# Supply_DAC.net
KiCad netlist of a schematic drawn in Altium Designer
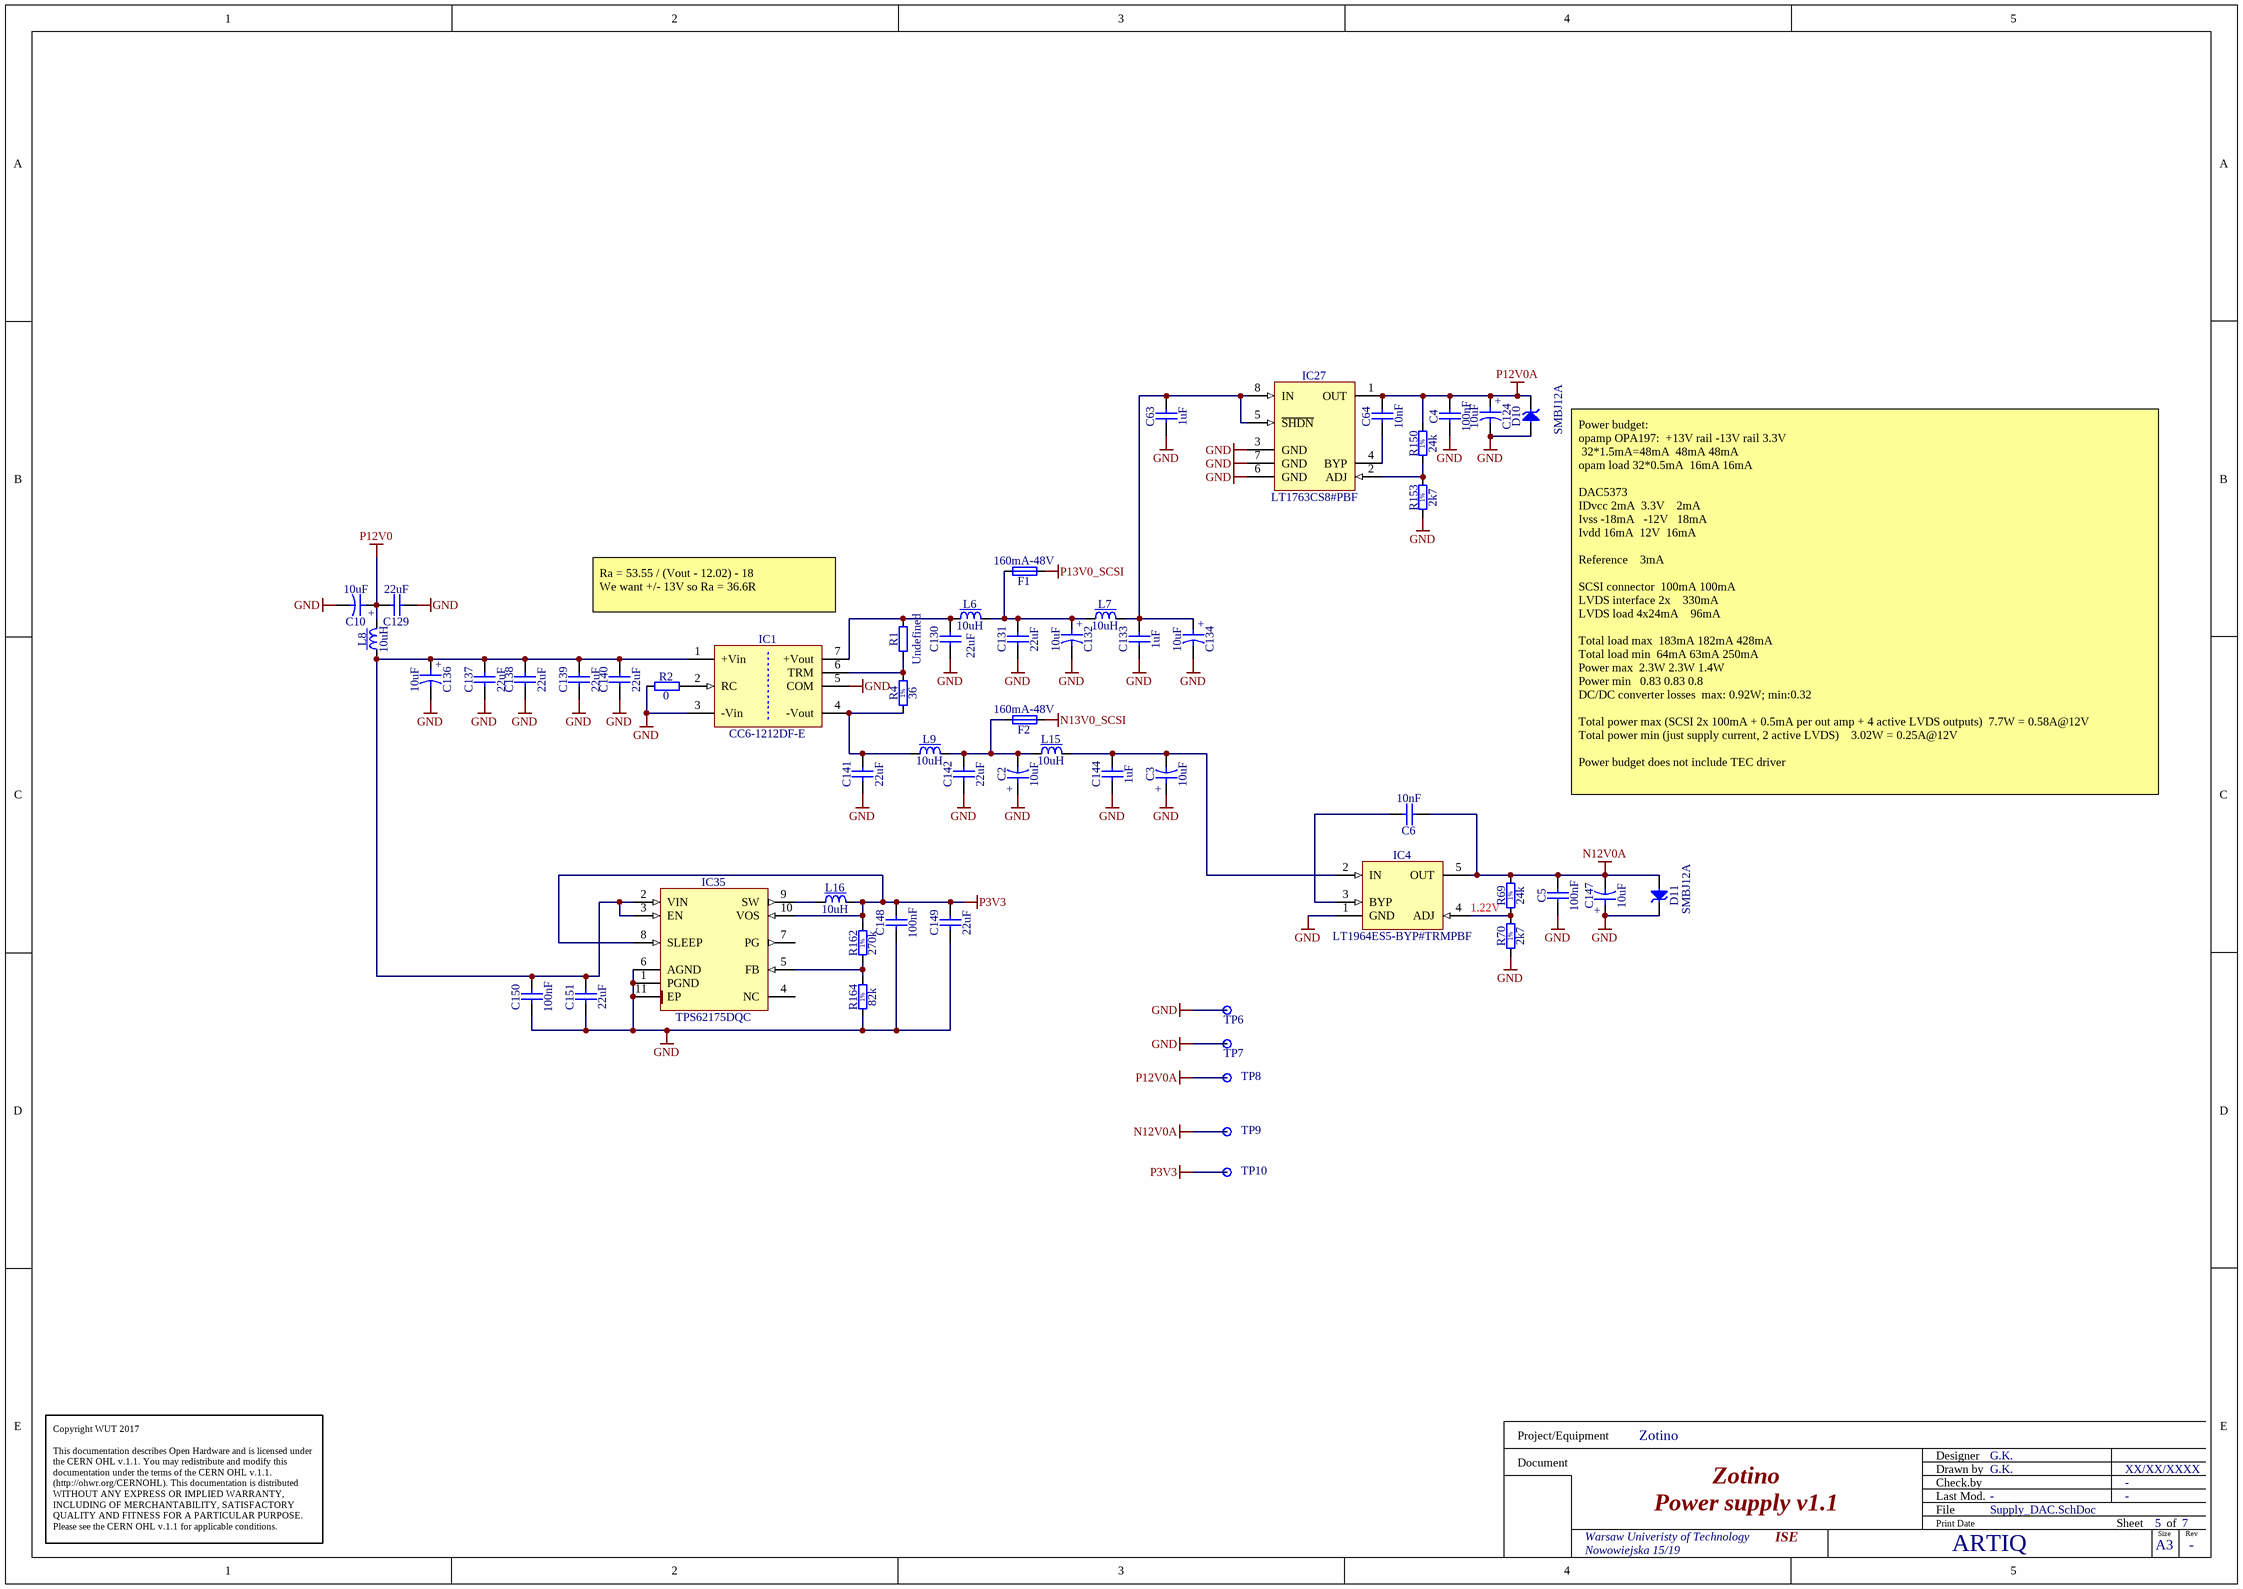
[diagram p0: Supply_DAC.SchDoc]

(export (version "E")
  (design (tool "Eeschema 10.0.6"))
  (components
    (comp (ref "C2")
      (value "10uF")
      (footprint "CAPMP3216X180N")
      (description "Polarised capacitor")
      (fields
        (field (name "PART NUMBER") "CTE3216-18_10UF_16V_20%_AVX_TCJ")
        (field (name "VOLTAGE") "16V")
        (field (name "AUTHOR") "CERN DEM JLC")
      )
      (libsource (lib "Capacitors") (part "Capacitor - polarized"))
    )
    (comp (ref "C3")
      (value "10uF")
      (footprint "CAPMP3216X180N")
      (description "Polarised capacitor")
      (fields
        (field (name "PART NUMBER") "CTE3216-18_10UF_16V_20%_AVX_TCJ")
        (field (name "VOLTAGE") "16V")
        (field (name "AUTHOR") "CERN DEM JLC")
      )
      (libsource (lib "Capacitors") (part "Capacitor - polarized"))
    )
    (comp (ref "C4")
      (value "100nF")
      (footprint "CAPC1005X55N")
      (description "Non-polarised capacitor")
      (fields
        (field (name "PART NUMBER") "CC0402_100NF_16V_10%_X5R")
        (field (name "VOLTAGE") "16V")
        (field (name "AUTHOR") "CERN DEM JLC")
      )
      (libsource (lib "Capacitors") (part "Capacitor - non polarized"))
    )
    (comp (ref "C5")
      (value "100nF")
      (footprint "CAPC1005X55N")
      (description "Non-polarised capacitor")
      (fields
        (field (name "PART NUMBER") "CC0402_100NF_16V_10%_X5R")
        (field (name "VOLTAGE") "16V")
        (field (name "AUTHOR") "CERN DEM JLC")
      )
      (libsource (lib "Capacitors") (part "Capacitor - non polarized"))
    )
    (comp (ref "C6")
      (value "10nF")
      (footprint "CAPC1608X87N")
      (description "Non-polarised capacitor")
      (fields
        (field (name "PART NUMBER") "CC0603_10NF_50V_10%_X7R")
        (field (name "VOLTAGE") "50V")
        (field (name "AUTHOR") "CERN DEM JLC")
      )
      (libsource (lib "Capacitors") (part "Capacitor - non polarized"))
    )
    (comp (ref "C10")
      (value "10uF")
      (footprint "CAPMP3216X180N")
      (description "Polarised capacitor")
      (fields
        (field (name "PART NUMBER") "CTE3216-18_10UF_16V_20%_AVX_TCJ")
        (field (name "VOLTAGE") "16V")
        (field (name "AUTHOR") "CERN DEM JLC")
      )
      (libsource (lib "Capacitors") (part "Capacitor - polarized"))
    )
    (comp (ref "C63")
      (value "1uF")
      (footprint "CAPC1608X87N")
      (description "Non-polarised capacitor")
      (fields
        (field (name "PART NUMBER") "CC0603_1UF_25V_10%_X7R")
        (field (name "VOLTAGE") "25V")
        (field (name "AUTHOR") "CERN DEM JLC")
      )
      (libsource (lib "Capacitors") (part "Capacitor - non polarized"))
    )
    (comp (ref "C64")
      (value "10nF")
      (footprint "CAPC1608X87N")
      (description "Non-polarised capacitor")
      (fields
        (field (name "PART NUMBER") "CC0603_10NF_50V_10%_X7R")
        (field (name "VOLTAGE") "50V")
        (field (name "AUTHOR") "CERN DEM JLC")
      )
      (libsource (lib "Capacitors") (part "Capacitor - non polarized"))
    )
    (comp (ref "C124")
      (value "10uF")
      (footprint "CAPMP3216X180N")
      (description "Polarised capacitor")
      (fields
        (field (name "PART NUMBER") "CTE3216-18_10UF_16V_20%_AVX_TCJ")
        (field (name "VOLTAGE") "16V")
        (field (name "AUTHOR") "CERN DEM JLC")
      )
      (libsource (lib "Capacitors") (part "Capacitor - polarized"))
    )
    (comp (ref "C129")
      (value "22uF")
      (footprint "CAPC2012X135N")
      (description "Non-polarised capacitor")
      (fields
        (field (name "PART NUMBER") "CC0805_22UF_16V_10%_X5R")
        (field (name "VOLTAGE") "16V")
        (field (name "AUTHOR") "CERN DEM JLC")
      )
      (libsource (lib "Capacitors") (part "Capacitor - non polarized"))
    )
    (comp (ref "C130")
      (value "22uF")
      (footprint "CAPC2012X135N")
      (description "Non-polarised capacitor")
      (fields
        (field (name "PART NUMBER") "CC0805_22UF_16V_10%_X5R")
        (field (name "VOLTAGE") "16V")
        (field (name "AUTHOR") "CERN DEM JLC")
      )
      (libsource (lib "Capacitors") (part "Capacitor - non polarized"))
    )
    (comp (ref "C131")
      (value "22uF")
      (footprint "CAPC2012X135N")
      (description "Non-polarised capacitor")
      (fields
        (field (name "PART NUMBER") "CC0805_22UF_16V_10%_X5R")
        (field (name "VOLTAGE") "16V")
        (field (name "AUTHOR") "CERN DEM JLC")
      )
      (libsource (lib "Capacitors") (part "Capacitor - non polarized"))
    )
    (comp (ref "C132")
      (value "10uF")
      (footprint "CAPMP3216X180N")
      (description "Polarised capacitor")
      (fields
        (field (name "PART NUMBER") "CTE3216-18_10UF_16V_20%_AVX_TCJ")
        (field (name "VOLTAGE") "16V")
        (field (name "AUTHOR") "CERN DEM JLC")
      )
      (libsource (lib "Capacitors") (part "Capacitor - polarized"))
    )
    (comp (ref "C133")
      (value "1uF")
      (footprint "CAPC1608X87N")
      (description "Non-polarised capacitor")
      (fields
        (field (name "PART NUMBER") "CC0603_1UF_25V_10%_X7R")
        (field (name "VOLTAGE") "25V")
        (field (name "AUTHOR") "CERN DEM JLC")
      )
      (libsource (lib "Capacitors") (part "Capacitor - non polarized"))
    )
    (comp (ref "C134")
      (value "10uF")
      (footprint "CAPMP3216X180N")
      (description "Polarised capacitor")
      (fields
        (field (name "PART NUMBER") "CTE3216-18_10UF_16V_20%_AVX_TCJ")
        (field (name "VOLTAGE") "16V")
        (field (name "AUTHOR") "CERN DEM JLC")
      )
      (libsource (lib "Capacitors") (part "Capacitor - polarized"))
    )
    (comp (ref "C136")
      (value "10uF")
      (footprint "CAPMP3216X180N")
      (description "Polarised capacitor")
      (fields
        (field (name "PART NUMBER") "CTE3216-18_10UF_16V_20%_AVX_TCJ")
        (field (name "VOLTAGE") "16V")
        (field (name "AUTHOR") "CERN DEM JLC")
      )
      (libsource (lib "Capacitors") (part "Capacitor - polarized"))
    )
    (comp (ref "C137")
      (value "22uF")
      (footprint "CAPC2012X135N")
      (description "Non-polarised capacitor")
      (fields
        (field (name "PART NUMBER") "CC0805_22UF_16V_10%_X5R")
        (field (name "VOLTAGE") "16V")
        (field (name "AUTHOR") "CERN DEM JLC")
      )
      (libsource (lib "Capacitors") (part "Capacitor - non polarized"))
    )
    (comp (ref "C138")
      (value "22uF")
      (footprint "CAPC2012X135N")
      (description "Non-polarised capacitor")
      (fields
        (field (name "PART NUMBER") "CC0805_22UF_16V_10%_X5R")
        (field (name "VOLTAGE") "16V")
        (field (name "AUTHOR") "CERN DEM JLC")
      )
      (libsource (lib "Capacitors") (part "Capacitor - non polarized"))
    )
    (comp (ref "C139")
      (value "22uF")
      (footprint "CAPC2012X135N")
      (description "Non-polarised capacitor")
      (fields
        (field (name "PART NUMBER") "CC0805_22UF_16V_10%_X5R")
        (field (name "VOLTAGE") "16V")
        (field (name "AUTHOR") "CERN DEM JLC")
      )
      (libsource (lib "Capacitors") (part "Capacitor - non polarized"))
    )
    (comp (ref "C140")
      (value "22uF")
      (footprint "CAPC2012X135N")
      (description "Non-polarised capacitor")
      (fields
        (field (name "PART NUMBER") "CC0805_22UF_16V_10%_X5R")
        (field (name "VOLTAGE") "16V")
        (field (name "AUTHOR") "CERN DEM JLC")
      )
      (libsource (lib "Capacitors") (part "Capacitor - non polarized"))
    )
    (comp (ref "C141")
      (value "22uF")
      (footprint "CAPC2012X135N")
      (description "Non-polarised capacitor")
      (fields
        (field (name "PART NUMBER") "CC0805_22UF_16V_10%_X5R")
        (field (name "VOLTAGE") "16V")
        (field (name "AUTHOR") "CERN DEM JLC")
      )
      (libsource (lib "Capacitors") (part "Capacitor - non polarized"))
    )
    (comp (ref "C142")
      (value "22uF")
      (footprint "CAPC2012X135N")
      (description "Non-polarised capacitor")
      (fields
        (field (name "PART NUMBER") "CC0805_22UF_16V_10%_X5R")
        (field (name "VOLTAGE") "16V")
        (field (name "AUTHOR") "CERN DEM JLC")
      )
      (libsource (lib "Capacitors") (part "Capacitor - non polarized"))
    )
    (comp (ref "C144")
      (value "1uF")
      (footprint "CAPC1608X87N")
      (description "Non-polarised capacitor")
      (fields
        (field (name "PART NUMBER") "CC0603_1UF_25V_10%_X7R")
        (field (name "VOLTAGE") "25V")
        (field (name "AUTHOR") "CERN DEM JLC")
      )
      (libsource (lib "Capacitors") (part "Capacitor - non polarized"))
    )
    (comp (ref "C147")
      (value "10uF")
      (footprint "CAPMP3216X180N")
      (description "Polarised capacitor")
      (fields
        (field (name "PART NUMBER") "CTE3216-18_10UF_16V_20%_AVX_TCJ")
        (field (name "VOLTAGE") "16V")
        (field (name "AUTHOR") "CERN DEM JLC")
      )
      (libsource (lib "Capacitors") (part "Capacitor - polarized"))
    )
    (comp (ref "C148")
      (value "100nF")
      (footprint "CAPC1005X55N")
      (description "Non-polarised capacitor")
      (fields
        (field (name "PART NUMBER") "CC0402_100NF_16V_10%_X5R")
        (field (name "VOLTAGE") "16V")
        (field (name "AUTHOR") "CERN DEM JLC")
      )
      (libsource (lib "Capacitors") (part "Capacitor - non polarized"))
    )
    (comp (ref "C149")
      (value "22uF")
      (footprint "CAPC2012X135N")
      (description "Non-polarised capacitor")
      (fields
        (field (name "PART NUMBER") "CC0805_22UF_16V_10%_X5R")
        (field (name "VOLTAGE") "16V")
        (field (name "AUTHOR") "CERN DEM JLC")
      )
      (libsource (lib "Capacitors") (part "Capacitor - non polarized"))
    )
    (comp (ref "C150")
      (value "100nF")
      (footprint "CAPC1005X55N")
      (description "Non-polarised capacitor")
      (fields
        (field (name "PART NUMBER") "CC0402_100NF_16V_10%_X5R")
        (field (name "VOLTAGE") "16V")
        (field (name "AUTHOR") "CERN DEM JLC")
      )
      (libsource (lib "Capacitors") (part "Capacitor - non polarized"))
    )
    (comp (ref "C151")
      (value "22uF")
      (footprint "CAPC2012X135N")
      (description "Non-polarised capacitor")
      (fields
        (field (name "PART NUMBER") "CC0805_22UF_16V_10%_X5R")
        (field (name "VOLTAGE") "16V")
        (field (name "AUTHOR") "CERN DEM JLC")
      )
      (libsource (lib "Capacitors") (part "Capacitor - non polarized"))
    )
    (comp (ref "D10")
      (value "SMBJ12A")
      (footprint "DIOM5336X265N")
      (description "Zener Diode")
      (fields
        (field (name "VOLTAGE") "12V")
        (field (name "POWER") "600W")
        (field (name "AUTHOR") "CERN DEM JLC")
      )
      (libsource (lib "ICs And Semiconductors") (part "Diode Zener"))
    )
    (comp (ref "D11")
      (value "SMBJ12A")
      (footprint "DIOM5336X265N")
      (description "Zener Diode")
      (fields
        (field (name "VOLTAGE") "12V")
        (field (name "POWER") "600W")
        (field (name "AUTHOR") "CERN DEM JLC")
      )
      (libsource (lib "ICs And Semiconductors") (part "Diode Zener"))
    )
    (comp (ref "F1")
      (value "160mA-48V")
      (footprint "FUSRC3216X100N")
      (description "Fuse")
      (fields
        (field (name "PART NUMBER") "FUSR1206_TYCO-NANOSMD016F")
        (field (name "MANUFACTURER") "TYCO ELECTRONICS")
        (field (name "AUTHOR") "CERN DEM JLC")
      )
      (libsource (lib "Eletro-mechanical") (part "Fuse"))
    )
    (comp (ref "F2")
      (value "160mA-48V")
      (footprint "FUSRC3216X100N")
      (description "Fuse")
      (fields
        (field (name "PART NUMBER") "FUSR1206_TYCO-NANOSMD016F")
        (field (name "MANUFACTURER") "TYCO ELECTRONICS")
        (field (name "AUTHOR") "CERN DEM JLC")
      )
      (libsource (lib "Eletro-mechanical") (part "Fuse"))
    )
    (comp (ref "IC1")
      (value "CC6-1212DF-E")
      (footprint "CC6-1212DF-E")
      (description "CONV DC/DC 6W DUAL 12V +-12V PCB")
      (fields (field (name "MANUFACTURER") "TDK-Lambda Americas Inc.") (field (name "AUTHOR") "GK"))
      (libsource (lib "LIBRARY_SCH") (part "DC/DC_CC6-1212DF-E"))
    )
    (comp (ref "IC4")
      (value "LT1964ES5-BYP#TRMPBF")
      (footprint "SOT95P280X100-5N")
      (description "200mA, Low Noise, Low Dropout Negative Micropower Regulator")
      (fields (field (name "MANUFACTURER") "LINEAR TECHNOLOGY") (field (name "AUTHOR") "CERN DEM MR"))
      (libsource (lib "ICs And Semiconductors") (part "LT1964-BYP"))
    )
    (comp (ref "IC27")
      (value "LT1763CS8#PBF")
      (footprint "SOIC127P600X175-8N")
      (description "1.22V to 20V 500mA, Low Noise, LDO Adjustable Micropower Regulator")
      (fields (field (name "MANUFACTURER") "LINEAR TECHNOLOGY") (field (name "AUTHOR") "CERN DEM JLC"))
      (libsource (lib "ICs And Semiconductors") (part "LT1763xS8"))
    )
    (comp (ref "IC35")
      (value "TPS62175DQC")
      (footprint "SON50P200X300X80-11N-R94X250")
      (description "4.75-28VDC to 1-6VDC, 500mA Step-Down Converter With Sleep Mode")
      (fields (field (name "MANUFACTURER") "TEXAS INSTRUMENTS") (field (name "AUTHOR") "CERN DEM JMW"))
      (libsource (lib "ICs And Semiconductors") (part "TPS62175"))
    )
    (comp (ref "L6")
      (value "10uH")
      (footprint "IND_MURATA-PS_8400")
      (description "Inductor With Core")
      (fields
        (field (name "PART NUMBER") "IND_10UH_10%_MURATA-PS_8400")
        (field (name "POWER") "950mA")
        (field (name "AUTHOR") "CERN DEM JLC")
      )
      (libsource (lib "Inductors & Transformers") (part "Inductor With Magnetic core"))
    )
    (comp (ref "L7")
      (value "10uH")
      (footprint "IND_MURATA-PS_8400")
      (description "Inductor With Core")
      (fields
        (field (name "PART NUMBER") "IND_10UH_10%_MURATA-PS_8400")
        (field (name "POWER") "950mA")
        (field (name "AUTHOR") "CERN DEM JLC")
      )
      (libsource (lib "Inductors & Transformers") (part "Inductor With Magnetic core"))
    )
    (comp (ref "L8")
      (value "10uH")
      (footprint "IND_MURATA-PS_8400")
      (description "Inductor With Core")
      (fields
        (field (name "PART NUMBER") "IND_10UH_10%_MURATA-PS_8400")
        (field (name "POWER") "950mA")
        (field (name "AUTHOR") "CERN DEM JLC")
      )
      (libsource (lib "") (part "Inductor With Magnetic core_1"))
    )
    (comp (ref "L9")
      (value "10uH")
      (footprint "IND_MURATA-PS_8400")
      (description "Inductor With Core")
      (fields
        (field (name "PART NUMBER") "IND_10UH_10%_MURATA-PS_8400")
        (field (name "POWER") "950mA")
        (field (name "AUTHOR") "CERN DEM JLC")
      )
      (libsource (lib "Inductors & Transformers") (part "Inductor With Magnetic core"))
    )
    (comp (ref "L15")
      (value "10uH")
      (footprint "IND_MURATA-PS_8400")
      (description "Inductor With Core")
      (fields
        (field (name "PART NUMBER") "IND_10UH_10%_MURATA-PS_8400")
        (field (name "POWER") "950mA")
        (field (name "AUTHOR") "CERN DEM JLC")
      )
      (libsource (lib "Inductors & Transformers") (part "Inductor With Magnetic core"))
    )
    (comp (ref "L16")
      (value "10uH")
      (footprint "IND_MURATA-PS_8400")
      (description "Inductor With Core")
      (fields
        (field (name "PART NUMBER") "IND_10UH_10%_MURATA-PS_8400")
        (field (name "POWER") "950mA")
        (field (name "AUTHOR") "CERN DEM JLC")
      )
      (libsource (lib "Inductors & Transformers") (part "Inductor With Magnetic core"))
    )
    (comp (ref "R1")
      (value "Undefined")
      (footprint "RESC1608X55N")
      (description "Resistor")
      (fields (field (name "PART NUMBER") "R0603_NO-VALUE") (field (name "AUTHOR") "CERN DEM JLC"))
      (libsource (lib "Resistors") (part "Resistor"))
    )
    (comp (ref "R2")
      (value "0")
      (footprint "RESC1005X40N")
      (description "Resistor")
      (fields
        (field (name "PART NUMBER") "R0402_0R_JUMPER")
        (field (name "MANUFACTURER") "GENERIC")
        (field (name "AUTHOR") "CERN DEM JLC")
      )
      (libsource (lib "Resistors") (part "Resistor"))
    )
    (comp (ref "R4")
      (value "36")
      (footprint "RESC1608X55N")
      (description "Resistor - 1%")
      (fields
        (field (name "PART NUMBER") "R0603_36R_1%_0.1W_100PPM")
        (field (name "POWER") "0.1W")
        (field (name "AUTHOR") "CERN DEM JLC")
      )
      (libsource (lib "Resistors") (part "Resistor - 1%"))
    )
    (comp (ref "R69")
      (value "24k")
      (footprint "RESC1608X55N")
      (description "Resistor - 1%")
      (fields
        (field (name "PART NUMBER") "R0603_24K_1%_0.1W_100PPM")
        (field (name "POWER") "0.1W")
        (field (name "AUTHOR") "CERN DEM JLC")
      )
      (libsource (lib "Resistors") (part "Resistor - 1%"))
    )
    (comp (ref "R70")
      (value "2k7")
      (footprint "RESC1608X55N")
      (description "Resistor - 1%")
      (fields
        (field (name "PART NUMBER") "R0603_2K7_1%_0.1W_100PPM")
        (field (name "POWER") "0.1W")
        (field (name "AUTHOR") "CERN DEM JLC")
      )
      (libsource (lib "Resistors") (part "Resistor - 1%"))
    )
    (comp (ref "R150")
      (value "24k")
      (footprint "RESC1608X55N")
      (description "Resistor - 1%")
      (fields
        (field (name "PART NUMBER") "R0603_24K_1%_0.1W_100PPM")
        (field (name "POWER") "0.1W")
        (field (name "AUTHOR") "CERN DEM JLC")
      )
      (libsource (lib "Resistors") (part "Resistor - 1%"))
    )
    (comp (ref "R153")
      (value "2k7")
      (footprint "RESC1608X55N")
      (description "Resistor - 1%")
      (fields
        (field (name "PART NUMBER") "R0603_2K7_1%_0.1W_100PPM")
        (field (name "POWER") "0.1W")
        (field (name "AUTHOR") "CERN DEM JLC")
      )
      (libsource (lib "Resistors") (part "Resistor - 1%"))
    )
    (comp (ref "R162")
      (value "270k")
      (footprint "RESC1608X55N")
      (description "Resistor - 1%")
      (fields
        (field (name "PART NUMBER") "R0603_270K_1%_0.1W_100PPM")
        (field (name "POWER") "0.1W")
        (field (name "AUTHOR") "CERN DEM JLC")
      )
      (libsource (lib "Resistors") (part "Resistor - 1%"))
    )
    (comp (ref "R164")
      (value "82k")
      (footprint "RESC1608X55N")
      (description "Resistor - 1%")
      (fields
        (field (name "PART NUMBER") "R0603_82K_1%_0.1W_100PPM")
        (field (name "POWER") "0.1W")
        (field (name "AUTHOR") "CERN DEM JLC")
      )
      (libsource (lib "Resistors") (part "Resistor - 1%"))
    )
    (comp (ref "TP6")
      (value "Test Point")
      (footprint "TPS127")
      (fields (field (name "PART NUMBER") "SMD_PAD_1.27X1.27MM") (field (name "AUTHOR") "CERN DEM JLC"))
      (libsource (lib "Eletro-mechanical") (part "Test Point"))
    )
    (comp (ref "TP7")
      (value "Test Point")
      (footprint "TPS127")
      (fields (field (name "PART NUMBER") "SMD_PAD_1.27X1.27MM") (field (name "AUTHOR") "CERN DEM JLC"))
      (libsource (lib "Eletro-mechanical") (part "Test Point"))
    )
    (comp (ref "TP8")
      (value "Test Point")
      (footprint "TPS127")
      (fields (field (name "PART NUMBER") "SMD_PAD_1.27X1.27MM") (field (name "AUTHOR") "CERN DEM JLC"))
      (libsource (lib "Eletro-mechanical") (part "Test Point"))
    )
    (comp (ref "TP9")
      (value "Test Point")
      (footprint "TPS127")
      (fields (field (name "PART NUMBER") "SMD_PAD_1.27X1.27MM") (field (name "AUTHOR") "CERN DEM JLC"))
      (libsource (lib "Eletro-mechanical") (part "Test Point"))
    )
    (comp (ref "TP10")
      (value "Test Point")
      (footprint "TPS127")
      (fields (field (name "PART NUMBER") "SMD_PAD_1.27X1.27MM") (field (name "AUTHOR") "CERN DEM JLC"))
      (libsource (lib "Eletro-mechanical") (part "Test Point"))
    )
  )
  (nets
    (net (code "1") (name "GND") (class "Default")
      (node (ref "C10") (pin "2") (pinfunction "2_2") (pintype "passive"))
      (node (ref "C124") (pin "2") (pinfunction "2_2") (pintype "passive"))
      (node (ref "C129") (pin "1") (pinfunction "1_1") (pintype "passive"))
      (node (ref "C130") (pin "1") (pinfunction "1_1") (pintype "passive"))
      (node (ref "C131") (pin "1") (pinfunction "1_1") (pintype "passive"))
      (node (ref "C132") (pin "2") (pinfunction "2_2") (pintype "passive"))
      (node (ref "C133") (pin "1") (pinfunction "1_1") (pintype "passive"))
      (node (ref "C134") (pin "2") (pinfunction "2_2") (pintype "passive"))
      (node (ref "C136") (pin "2") (pinfunction "2_2") (pintype "passive"))
      (node (ref "C137") (pin "1") (pinfunction "1_1") (pintype "passive"))
      (node (ref "C138") (pin "1") (pinfunction "1_1") (pintype "passive"))
      (node (ref "C139") (pin "1") (pinfunction "1_1") (pintype "passive"))
      (node (ref "C140") (pin "1") (pinfunction "1_1") (pintype "passive"))
      (node (ref "C141") (pin "1") (pinfunction "1_1") (pintype "passive"))
      (node (ref "C142") (pin "1") (pinfunction "1_1") (pintype "passive"))
      (node (ref "C144") (pin "1") (pinfunction "1_1") (pintype "passive"))
      (node (ref "C147") (pin "1") (pinfunction "1_1") (pintype "passive"))
      (node (ref "C148") (pin "1") (pinfunction "1_1") (pintype "passive"))
      (node (ref "C149") (pin "1") (pinfunction "1_1") (pintype "passive"))
      (node (ref "C150") (pin "1") (pinfunction "1_1") (pintype "passive"))
      (node (ref "C151") (pin "1") (pinfunction "1_1") (pintype "passive"))
      (node (ref "C2") (pin "1") (pinfunction "1_1") (pintype "passive"))
      (node (ref "C3") (pin "1") (pinfunction "1_1") (pintype "passive"))
      (node (ref "C4") (pin "1") (pinfunction "1_1") (pintype "passive"))
      (node (ref "C5") (pin "1") (pinfunction "1_1") (pintype "passive"))
      (node (ref "C63") (pin "1") (pinfunction "1_1") (pintype "passive"))
      (node (ref "D10") (pin "2") (pinfunction "A_2") (pintype "passive"))
      (node (ref "D11") (pin "1") (pinfunction "C_1") (pintype "passive"))
      (node (ref "IC1") (pin "3") (pinfunction "-Vin_3") (pintype "power_in"))
      (node (ref "IC1") (pin "5") (pinfunction "COM_5") (pintype "power_in"))
      (node (ref "IC27") (pin "3") (pinfunction "GND_3") (pintype "power_in"))
      (node (ref "IC27") (pin "6") (pinfunction "GND_6") (pintype "power_in"))
      (node (ref "IC27") (pin "7") (pinfunction "GND_7") (pintype "power_in"))
      (node (ref "IC35") (pin "1") (pinfunction "PGND_1") (pintype "power_in"))
      (node (ref "IC35") (pin "11") (pinfunction "EP_11") (pintype "power_in"))
      (node (ref "IC35") (pin "6") (pinfunction "AGND_6") (pintype "power_in"))
      (node (ref "IC4") (pin "1") (pinfunction "GND_1") (pintype "power_in"))
      (node (ref "R153") (pin "1") (pinfunction "1_1") (pintype "passive"))
      (node (ref "R164") (pin "1") (pinfunction "1_1") (pintype "passive"))
      (node (ref "R2") (pin "1") (pinfunction "1_1") (pintype "passive"))
      (node (ref "R70") (pin "1") (pinfunction "1_1") (pintype "passive"))
      (node (ref "TP6") (pin "1") (pinfunction "1_1") (pintype "bidirectional"))
      (node (ref "TP7") (pin "1") (pinfunction "1_1") (pintype "bidirectional"))
    )
    (net (code "2") (name "N12V0A") (class "Default")
      (node (ref "C147") (pin "2") (pinfunction "2_2") (pintype "passive"))
      (node (ref "C5") (pin "2") (pinfunction "2_2") (pintype "passive"))
      (node (ref "C6") (pin "1") (pinfunction "1_1") (pintype "passive"))
      (node (ref "D11") (pin "2") (pinfunction "A_2") (pintype "passive"))
      (node (ref "IC4") (pin "5") (pinfunction "OUT_5") (pintype "power_in"))
      (node (ref "R69") (pin "2") (pinfunction "2_2") (pintype "passive"))
      (node (ref "TP9") (pin "1") (pinfunction "1_1") (pintype "bidirectional"))
    )
    (net (code "3") (name "N13V0_SCSI") (class "Default")
      (node (ref "F2") (pin "1") (pinfunction "1_1") (pintype "passive"))
    )
    (net (code "4") (name "Net-(C131-Pad2)") (class "Default")
      (node (ref "C131") (pin "2") (pinfunction "2_2") (pintype "passive"))
      (node (ref "C132") (pin "1") (pinfunction "1_1") (pintype "passive"))
      (node (ref "F1") (pin "2") (pinfunction "2_2") (pintype "passive"))
      (node (ref "L6") (pin "2") (pinfunction "2_2") (pintype "passive"))
      (node (ref "L7") (pin "1") (pinfunction "1_1") (pintype "passive"))
    )
    (net (code "5") (name "Net-(C142-Pad2)") (class "Default")
      (node (ref "C142") (pin "2") (pinfunction "2_2") (pintype "passive"))
      (node (ref "C2") (pin "2") (pinfunction "2_2") (pintype "passive"))
      (node (ref "F2") (pin "2") (pinfunction "2_2") (pintype "passive"))
      (node (ref "L15") (pin "1") (pinfunction "1_1") (pintype "passive"))
      (node (ref "L9") (pin "2") (pinfunction "2_2") (pintype "passive"))
    )
    (net (code "6") (name "Net-(IC1-+Vin)") (class "Default")
      (node (ref "C136") (pin "1") (pinfunction "1_1") (pintype "passive"))
      (node (ref "C137") (pin "2") (pinfunction "2_2") (pintype "passive"))
      (node (ref "C138") (pin "2") (pinfunction "2_2") (pintype "passive"))
      (node (ref "C139") (pin "2") (pinfunction "2_2") (pintype "passive"))
      (node (ref "C140") (pin "2") (pinfunction "2_2") (pintype "passive"))
      (node (ref "C150") (pin "2") (pinfunction "2_2") (pintype "passive"))
      (node (ref "C151") (pin "2") (pinfunction "2_2") (pintype "passive"))
      (node (ref "IC1") (pin "1") (pinfunction "+Vin_1") (pintype "power_in"))
      (node (ref "IC35") (pin "2") (pinfunction "VIN_2") (pintype "input"))
      (node (ref "IC35") (pin "3") (pinfunction "EN_3") (pintype "input"))
      (node (ref "L8") (pin "1") (pinfunction "1_1") (pintype "passive"))
    )
    (net (code "7") (name "Net-(IC1-+Vout)") (class "Default")
      (node (ref "C130") (pin "2") (pinfunction "2_2") (pintype "passive"))
      (node (ref "IC1") (pin "7") (pinfunction "+Vout_7") (pintype "power_in"))
      (node (ref "L6") (pin "1") (pinfunction "1_1") (pintype "passive"))
      (node (ref "R1") (pin "2") (pinfunction "2_2") (pintype "passive"))
    )
    (net (code "8") (name "Net-(IC1--Vout)") (class "Default")
      (node (ref "C141") (pin "2") (pinfunction "2_2") (pintype "passive"))
      (node (ref "IC1") (pin "4") (pinfunction "-Vout_4") (pintype "power_in"))
      (node (ref "L9") (pin "1") (pinfunction "1_1") (pintype "passive"))
      (node (ref "R4") (pin "1") (pinfunction "1_1") (pintype "passive"))
    )
    (net (code "9") (name "Net-(IC1-RC)") (class "Default")
      (node (ref "IC1") (pin "2") (pinfunction "RC_2") (pintype "input"))
      (node (ref "R2") (pin "2") (pinfunction "2_2") (pintype "passive"))
    )
    (net (code "10") (name "Net-(IC1-TRM)") (class "Default")
      (node (ref "IC1") (pin "6") (pinfunction "TRM_6") (pintype "power_in"))
      (node (ref "R1") (pin "1") (pinfunction "1_1") (pintype "passive"))
      (node (ref "R4") (pin "2") (pinfunction "2_2") (pintype "passive"))
    )
    (net (code "11") (name "Net-(IC4-ADJ)") (class "Default")
      (node (ref "IC4") (pin "4") (pinfunction "ADJ_4") (pintype "input"))
      (node (ref "R69") (pin "1") (pinfunction "1_1") (pintype "passive"))
      (node (ref "R70") (pin "2") (pinfunction "2_2") (pintype "passive"))
    )
    (net (code "12") (name "Net-(IC4-BYP)") (class "Default")
      (node (ref "C6") (pin "2") (pinfunction "2_2") (pintype "passive"))
      (node (ref "IC4") (pin "3") (pinfunction "BYP_3") (pintype "input"))
    )
    (net (code "13") (name "Net-(IC4-IN)") (class "Default")
      (node (ref "C144") (pin "2") (pinfunction "2_2") (pintype "passive"))
      (node (ref "C3") (pin "2") (pinfunction "2_2") (pintype "passive"))
      (node (ref "IC4") (pin "2") (pinfunction "IN_2") (pintype "input"))
      (node (ref "L15") (pin "2") (pinfunction "2_2") (pintype "passive"))
    )
    (net (code "14") (name "Net-(IC27-ADJ)") (class "Default")
      (node (ref "IC27") (pin "2") (pinfunction "ADJ_2") (pintype "input"))
      (node (ref "R150") (pin "1") (pinfunction "1_1") (pintype "passive"))
      (node (ref "R153") (pin "2") (pinfunction "2_2") (pintype "passive"))
    )
    (net (code "15") (name "Net-(IC27-BYP)") (class "Default")
      (node (ref "C64") (pin "1") (pinfunction "1_1") (pintype "passive"))
      (node (ref "IC27") (pin "4") (pinfunction "BYP_4") (pintype "passive"))
    )
    (net (code "16") (name "Net-(IC27-IN)") (class "Default")
      (node (ref "C133") (pin "2") (pinfunction "2_2") (pintype "passive"))
      (node (ref "C134") (pin "1") (pinfunction "1_1") (pintype "passive"))
      (node (ref "C63") (pin "2") (pinfunction "2_2") (pintype "passive"))
      (node (ref "IC27") (pin "5") (pinfunction "~{SHDN}_5") (pintype "input"))
      (node (ref "IC27") (pin "8") (pinfunction "IN_8") (pintype "input"))
      (node (ref "L7") (pin "2") (pinfunction "2_2") (pintype "passive"))
    )
    (net (code "17") (name "Net-(IC35-FB)") (class "Default")
      (node (ref "IC35") (pin "5") (pinfunction "FB_5") (pintype "input"))
      (node (ref "R162") (pin "1") (pinfunction "1_1") (pintype "passive"))
      (node (ref "R164") (pin "2") (pinfunction "2_2") (pintype "passive"))
    )
    (net (code "18") (name "Net-(IC35-SW)") (class "Default")
      (node (ref "IC35") (pin "9") (pinfunction "SW_9") (pintype "output"))
      (node (ref "L16") (pin "1") (pinfunction "1_1") (pintype "passive"))
    )
    (net (code "19") (name "P3V3") (class "Default")
      (node (ref "C148") (pin "2") (pinfunction "2_2") (pintype "passive"))
      (node (ref "C149") (pin "2") (pinfunction "2_2") (pintype "passive"))
      (node (ref "IC35") (pin "10") (pinfunction "VOS_10") (pintype "input"))
      (node (ref "IC35") (pin "8") (pinfunction "SLEEP_8") (pintype "input"))
      (node (ref "L16") (pin "2") (pinfunction "2_2") (pintype "passive"))
      (node (ref "R162") (pin "2") (pinfunction "2_2") (pintype "passive"))
      (node (ref "TP10") (pin "1") (pinfunction "1_1") (pintype "bidirectional"))
    )
    (net (code "20") (name "P12V0") (class "Default")
      (node (ref "C10") (pin "1") (pinfunction "1_1") (pintype "passive"))
      (node (ref "C129") (pin "2") (pinfunction "2_2") (pintype "passive"))
      (node (ref "L8") (pin "2") (pinfunction "2_2") (pintype "passive"))
    )
    (net (code "21") (name "P12V0A") (class "Default")
      (node (ref "C124") (pin "1") (pinfunction "1_1") (pintype "passive"))
      (node (ref "C4") (pin "2") (pinfunction "2_2") (pintype "passive"))
      (node (ref "C64") (pin "2") (pinfunction "2_2") (pintype "passive"))
      (node (ref "D10") (pin "1") (pinfunction "C_1") (pintype "passive"))
      (node (ref "IC27") (pin "1") (pinfunction "OUT_1") (pintype "power_in"))
      (node (ref "R150") (pin "2") (pinfunction "2_2") (pintype "passive"))
      (node (ref "TP8") (pin "1") (pinfunction "1_1") (pintype "bidirectional"))
    )
    (net (code "22") (name "P13V0_SCSI") (class "Default")
      (node (ref "F1") (pin "1") (pinfunction "1_1") (pintype "passive"))
    )
    (net (code "23") (name "unconnected-(IC35-NC-Pad4)") (class "Default")
      (node (ref "IC35") (pin "4") (pinfunction "NC_4") (pintype "passive"))
    )
    (net (code "24") (name "unconnected-(IC35-PG-Pad7)") (class "Default")
      (node (ref "IC35") (pin "7") (pinfunction "PG_7") (pintype "output"))
    )
  )
)
